# pdb_v3.net
KiCad netlist of a schematic drawn in EAGLE
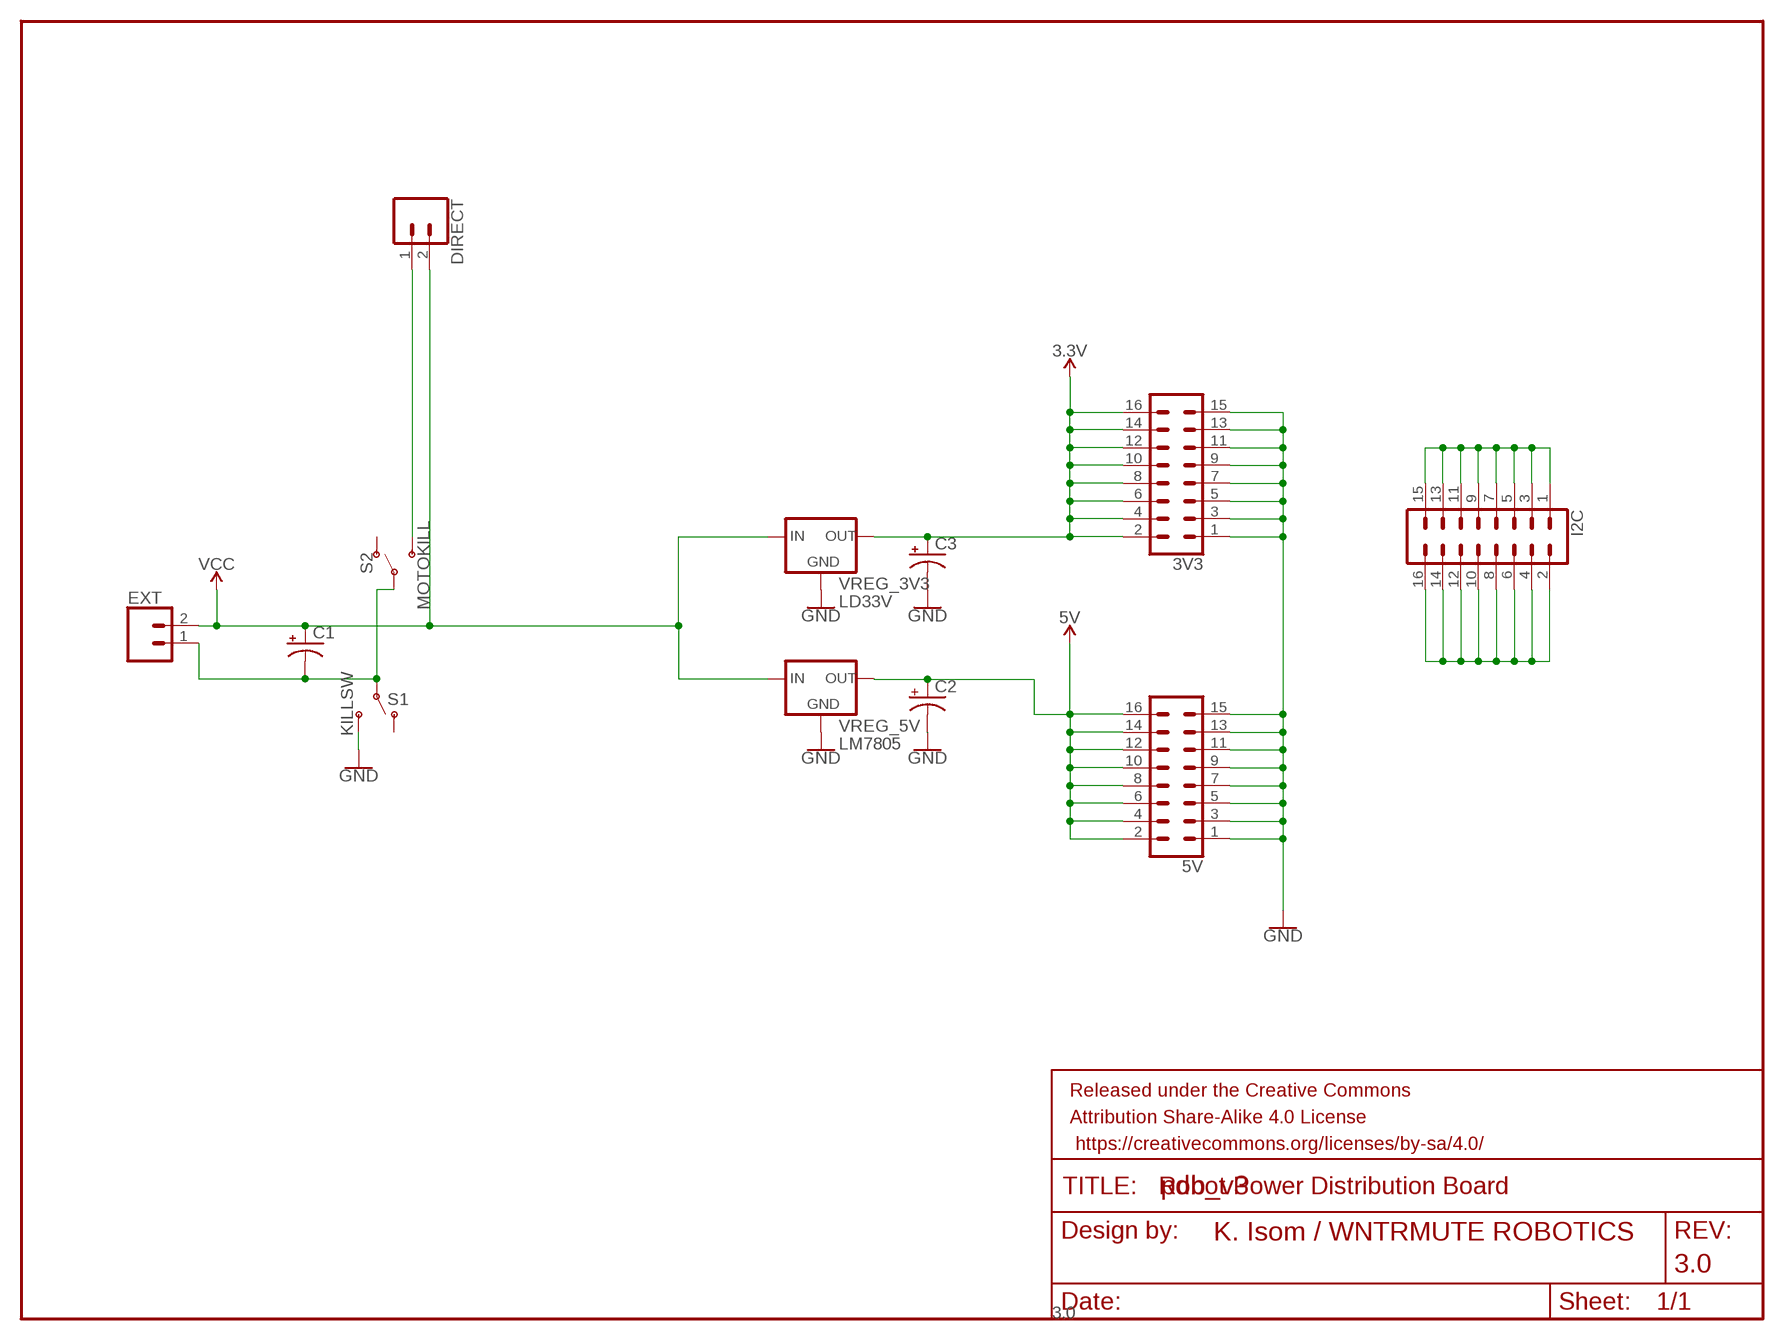
[diagram p0: schematic, sheet 1]

(export (version "E")
  (design (tool "Eeschema 10.0.6"))
  (components
    (comp (ref "3V3")
      (value "CONN_08X2_HEADER")
      (footprint "eagle-import:2X8")
      (libsource (lib "eagle-import") (part "CONN_08X2_HEADER"))
    )
    (comp (ref "5V")
      (value "CONN_08X2_HEADER")
      (footprint "eagle-import:2X8")
      (libsource (lib "eagle-import") (part "CONN_08X2_HEADER"))
    )
    (comp (ref "C1")
      (value "1000uF")
      (footprint "eagle-import:CPOL-RADIAL-5MM-10MM")
      (libsource (lib "eagle-import") (part "1000UF-RADIAL-5MM-25V-20%"))
    )
    (comp (ref "C2")
      (value "100uF")
      (footprint "eagle-import:E5-8,5")
      (libsource (lib "eagle-import") (part "CPOL-USE5-8.5"))
    )
    (comp (ref "C3")
      (value "100uF")
      (footprint "eagle-import:E5-8,5")
      (libsource (lib "eagle-import") (part "CPOL-USE5-8.5"))
    )
    (comp (ref "DIRECT")
      (value "CONN_025MM")
      (footprint "eagle-import:SCREWTERMINAL-5MM-2")
      (libsource (lib "eagle-import") (part "CONN_025MM"))
    )
    (comp (ref "EXT")
      (value "CONN_025MM")
      (footprint "eagle-import:SCREWTERMINAL-5MM-2")
      (libsource (lib "eagle-import") (part "CONN_025MM"))
    )
    (comp (ref "FRAME1")
      (value "FRAME-LETTERNO_PACKAGE")
      (footprint "eagle-import:DUMMY")
      (fields
        (field (name "DESIGNER") "K. Isom / WNTRMUTE ROBOTICS")
        (field (name "REV") "3.0")
        (field (name "VERSION") "3.0")
        (field (name "DESIGNER_1") "K. Isom / WNTRMUTE ROBOTICS")
        (field (name "VERSION_1") "3.0")
      )
      (libsource (lib "eagle-import") (part "FRAME-LETTERNO_PACKAGE"))
    )
    (comp (ref "I2C")
      (value "CONN_08X2_HEADER")
      (footprint "eagle-import:2X8")
      (libsource (lib "eagle-import") (part "CONN_08X2_HEADER"))
    )
    (comp (ref "S1")
      (value "KILLSW")
      (footprint "eagle-import:SWITCH_SPDT_PTH_11.6X4.0MM_LOCK")
      (libsource (lib "eagle-import") (part "SWITCH-SPDT-PTH-11.6X4.0MM-LOCK"))
    )
    (comp (ref "S2")
      (value "MOTOKILL")
      (footprint "eagle-import:SWITCH_SPDT_PTH_11.6X4.0MM_LOCK")
      (libsource (lib "eagle-import") (part "SWITCH-SPDT-PTH-11.6X4.0MM-LOCK"))
    )
    (comp (ref "VREG_3V3")
      (value "LD33V")
      (footprint "eagle-import:78XXL")
      (libsource (lib "eagle-import") (part "V_REG_LD1117VXX"))
    )
    (comp (ref "VREG_5V")
      (value "LM7805")
      (footprint "eagle-import:TO-220-ALT")
      (libsource (lib "eagle-import") (part "V_REG_78XX-TO-220"))
    )
  )
  (nets
    (net (code "1") (name "3.3V") (class "Default")
      (node (ref "3V3") (pin "10") (pinfunction "10_10") (pintype "passive"))
      (node (ref "3V3") (pin "12") (pinfunction "12_12") (pintype "passive"))
      (node (ref "3V3") (pin "14") (pinfunction "14_14") (pintype "passive"))
      (node (ref "3V3") (pin "16") (pinfunction "16_16") (pintype "passive"))
      (node (ref "3V3") (pin "2") (pinfunction "2_2") (pintype "passive"))
      (node (ref "3V3") (pin "4") (pinfunction "4_4") (pintype "passive"))
      (node (ref "3V3") (pin "6") (pinfunction "6_6") (pintype "passive"))
      (node (ref "3V3") (pin "8") (pinfunction "8_8") (pintype "passive"))
      (node (ref "C3") (pin "+") (pinfunction "+_+") (pintype "passive"))
      (node (ref "VREG_3V3") (pin "GND") (pinfunction "OUT_GND") (pintype "passive"))
    )
    (net (code "2") (name "5V") (class "Default")
      (node (ref "5V") (pin "10") (pinfunction "10_10") (pintype "passive"))
      (node (ref "5V") (pin "12") (pinfunction "12_12") (pintype "passive"))
      (node (ref "5V") (pin "14") (pinfunction "14_14") (pintype "passive"))
      (node (ref "5V") (pin "16") (pinfunction "16_16") (pintype "passive"))
      (node (ref "5V") (pin "2") (pinfunction "2_2") (pintype "passive"))
      (node (ref "5V") (pin "4") (pinfunction "4_4") (pintype "passive"))
      (node (ref "5V") (pin "6") (pinfunction "6_6") (pintype "passive"))
      (node (ref "5V") (pin "8") (pinfunction "8_8") (pintype "passive"))
      (node (ref "C2") (pin "+") (pinfunction "+_+") (pintype "passive"))
      (node (ref "VREG_5V") (pin "OUT") (pinfunction "OUT_OUT") (pintype "passive"))
    )
    (net (code "3") (name "GND") (class "Default")
      (node (ref "3V3") (pin "1") (pinfunction "1_1") (pintype "passive"))
      (node (ref "3V3") (pin "11") (pinfunction "11_11") (pintype "passive"))
      (node (ref "3V3") (pin "13") (pinfunction "13_13") (pintype "passive"))
      (node (ref "3V3") (pin "15") (pinfunction "15_15") (pintype "passive"))
      (node (ref "3V3") (pin "3") (pinfunction "3_3") (pintype "passive"))
      (node (ref "3V3") (pin "5") (pinfunction "5_5") (pintype "passive"))
      (node (ref "3V3") (pin "7") (pinfunction "7_7") (pintype "passive"))
      (node (ref "3V3") (pin "9") (pinfunction "9_9") (pintype "passive"))
      (node (ref "5V") (pin "1") (pinfunction "1_1") (pintype "passive"))
      (node (ref "5V") (pin "11") (pinfunction "11_11") (pintype "passive"))
      (node (ref "5V") (pin "13") (pinfunction "13_13") (pintype "passive"))
      (node (ref "5V") (pin "15") (pinfunction "15_15") (pintype "passive"))
      (node (ref "5V") (pin "3") (pinfunction "3_3") (pintype "passive"))
      (node (ref "5V") (pin "5") (pinfunction "5_5") (pintype "passive"))
      (node (ref "5V") (pin "7") (pinfunction "7_7") (pintype "passive"))
      (node (ref "5V") (pin "9") (pinfunction "9_9") (pintype "passive"))
      (node (ref "C2") (pin "-") (pinfunction "-_-") (pintype "passive"))
      (node (ref "C3") (pin "-") (pinfunction "-_-") (pintype "passive"))
      (node (ref "S1") (pin "3") (pinfunction "S_3") (pintype "passive"))
      (node (ref "VREG_3V3") (pin "IN") (pinfunction "GND_IN") (pintype "input"))
      (node (ref "VREG_5V") (pin "GND") (pinfunction "GND_GND") (pintype "input"))
    )
    (net (code "4") (name "Net-(I2C-Pad1)") (class "Default")
      (node (ref "I2C") (pin "1") (pinfunction "1_1") (pintype "passive"))
      (node (ref "I2C") (pin "11") (pinfunction "11_11") (pintype "passive"))
      (node (ref "I2C") (pin "13") (pinfunction "13_13") (pintype "passive"))
      (node (ref "I2C") (pin "15") (pinfunction "15_15") (pintype "passive"))
      (node (ref "I2C") (pin "3") (pinfunction "3_3") (pintype "passive"))
      (node (ref "I2C") (pin "5") (pinfunction "5_5") (pintype "passive"))
      (node (ref "I2C") (pin "7") (pinfunction "7_7") (pintype "passive"))
      (node (ref "I2C") (pin "9") (pinfunction "9_9") (pintype "passive"))
    )
    (net (code "5") (name "Net-(I2C-Pad10)") (class "Default")
      (node (ref "I2C") (pin "10") (pinfunction "10_10") (pintype "passive"))
      (node (ref "I2C") (pin "12") (pinfunction "12_12") (pintype "passive"))
      (node (ref "I2C") (pin "14") (pinfunction "14_14") (pintype "passive"))
      (node (ref "I2C") (pin "16") (pinfunction "16_16") (pintype "passive"))
      (node (ref "I2C") (pin "2") (pinfunction "2_2") (pintype "passive"))
      (node (ref "I2C") (pin "4") (pinfunction "4_4") (pintype "passive"))
      (node (ref "I2C") (pin "6") (pinfunction "6_6") (pintype "passive"))
      (node (ref "I2C") (pin "8") (pinfunction "8_8") (pintype "passive"))
    )
    (net (code "6") (name "Net-(S1-P)") (class "Default")
      (node (ref "C1") (pin "-") (pinfunction "-_-") (pintype "passive"))
      (node (ref "EXT") (pin "1") (pinfunction "1_1") (pintype "passive"))
      (node (ref "S1") (pin "2") (pinfunction "P_2") (pintype "passive"))
      (node (ref "S2") (pin "2") (pinfunction "P_2") (pintype "passive"))
    )
    (net (code "7") (name "Net-(S2-S)") (class "Default")
      (node (ref "DIRECT") (pin "1") (pinfunction "1_1") (pintype "passive"))
      (node (ref "S2") (pin "3") (pinfunction "S_3") (pintype "passive"))
    )
    (net (code "8") (name "VCC") (class "Default")
      (node (ref "C1") (pin "+") (pinfunction "+_+") (pintype "passive"))
      (node (ref "DIRECT") (pin "2") (pinfunction "2_2") (pintype "passive"))
      (node (ref "EXT") (pin "2") (pinfunction "2_2") (pintype "passive"))
      (node (ref "VREG_3V3") (pin "OUT") (pinfunction "IN_OUT") (pintype "input"))
      (node (ref "VREG_5V") (pin "IN") (pinfunction "IN_IN") (pintype "input"))
    )
    (net (code "9") (name "unconnected-(S1-O-Pad1)") (class "Default")
      (node (ref "S1") (pin "1") (pinfunction "O_1") (pintype "passive"))
    )
    (net (code "10") (name "unconnected-(S2-O-Pad1)") (class "Default")
      (node (ref "S2") (pin "1") (pinfunction "O_1") (pintype "passive"))
    )
  )
)
